# MCX_connectors_board.net
KiCad netlist of a schematic drawn in Altium Designer
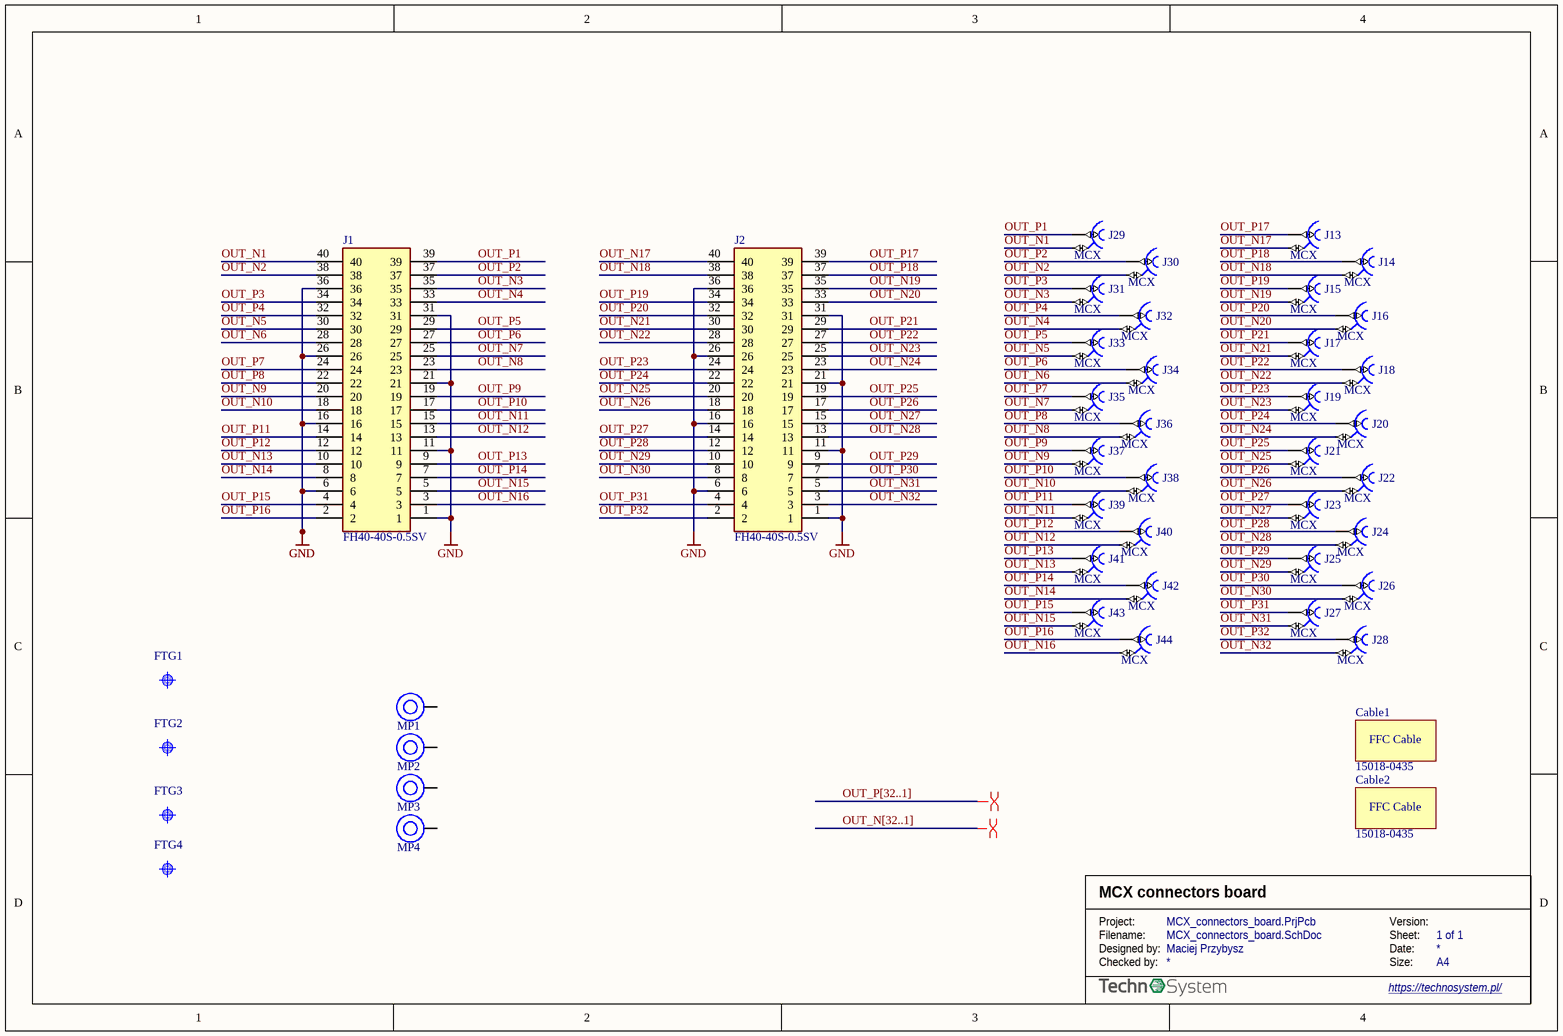
[diagram p0: MCX_connectors_board.SchDoc]

(export (version "E")
  (design (tool "Eeschema 10.0.6"))
  (components
    (comp (ref "Cable1")
      (value "15018-0435")
      (description "FFC Jumper Cables .5mm PremoFlex 40Ckt TypeA  Au 152mm")
      (libsource (lib "Integrated_Library_MP") (part "15018-0435"))
    )
    (comp (ref "Cable2")
      (value "15018-0435")
      (description "FFC Jumper Cables .5mm PremoFlex 40Ckt TypeA  Au 152mm")
      (libsource (lib "Integrated_Library_MP") (part "15018-0435"))
    )
    (comp (ref "FTG1")
      (value "Use only in PCB")
      (footprint "FIDUCIAL_TOP_C100-200")
      (description "Fiducial Target")
      (fields (field (name "PART NUMBER") "FIDUCIAL_TARGET_C100-200") (field (name "AUTHOR") "CERN DEM JLC"))
      (libsource (lib "Eletro-mechanical") (part "Fiducial Target"))
    )
    (comp (ref "FTG2")
      (value "Use only in PCB")
      (footprint "FIDUCIAL_TOP_C100-200")
      (description "Fiducial Target")
      (fields (field (name "PART NUMBER") "FIDUCIAL_TARGET_C100-200") (field (name "AUTHOR") "CERN DEM JLC"))
      (libsource (lib "Eletro-mechanical") (part "Fiducial Target"))
    )
    (comp (ref "FTG3")
      (value "Use only in PCB")
      (footprint "FIDUCIAL_TOP_C100-200")
      (description "Fiducial Target")
      (fields (field (name "PART NUMBER") "FIDUCIAL_TARGET_C100-200") (field (name "AUTHOR") "CERN DEM JLC"))
      (libsource (lib "Eletro-mechanical") (part "Fiducial Target"))
    )
    (comp (ref "FTG4")
      (value "Use only in PCB")
      (footprint "FIDUCIAL_TOP_C100-200")
      (description "Fiducial Target")
      (fields (field (name "PART NUMBER") "FIDUCIAL_TARGET_C100-200") (field (name "AUTHOR") "CERN DEM JLC"))
      (libsource (lib "Eletro-mechanical") (part "Fiducial Target"))
    )
    (comp (ref "J1")
      (value "FH40-40S-0.5SV")
      (footprint "FH4040S05SV")
      (description "Connector")
      (fields (field (name "MOUSER PART NUMBER") "798-FH40-40S-0.5SV"))
      (libsource (lib "Integrated_Library_LOADER") (part "FH40-40S-0.5SV"))
    )
    (comp (ref "J2")
      (value "FH40-40S-0.5SV")
      (footprint "FH4040S05SV")
      (description "Connector")
      (fields (field (name "MOUSER PART NUMBER") "798-FH40-40S-0.5SV"))
      (libsource (lib "Integrated_Library_LOADER") (part "FH40-40S-0.5SV"))
    )
    (comp (ref "J13")
      (value "MCX")
      (footprint "AMPHENOL_919-109J-51PX")
      (fields
        (field (name "PART NUMBER") "AMPHENOL_919-109J-51PX")
        (field (name "MANUFACTURER") "AMPHENOL")
        (field (name "MANUFACTURER PART NUMBER") "919-109J-51PX (MCX6251B1-3GT30G-50)")
        (field (name "AUTHOR") "CERN DEM BC")
      )
      (libsource (lib "Connectors") (part "Coax_1Female_1Shield"))
    )
    (comp (ref "J14")
      (value "MCX")
      (footprint "AMPHENOL_919-109J-51PX")
      (fields
        (field (name "PART NUMBER") "AMPHENOL_919-109J-51PX")
        (field (name "MANUFACTURER") "AMPHENOL")
        (field (name "MANUFACTURER PART NUMBER") "919-109J-51PX (MCX6251B1-3GT30G-50)")
        (field (name "AUTHOR") "CERN DEM BC")
      )
      (libsource (lib "Connectors") (part "Coax_1Female_1Shield"))
    )
    (comp (ref "J15")
      (value "MCX")
      (footprint "AMPHENOL_919-109J-51PX")
      (fields
        (field (name "PART NUMBER") "AMPHENOL_919-109J-51PX")
        (field (name "MANUFACTURER") "AMPHENOL")
        (field (name "MANUFACTURER PART NUMBER") "919-109J-51PX (MCX6251B1-3GT30G-50)")
        (field (name "AUTHOR") "CERN DEM BC")
      )
      (libsource (lib "Connectors") (part "Coax_1Female_1Shield"))
    )
    (comp (ref "J16")
      (value "MCX")
      (footprint "AMPHENOL_919-109J-51PX")
      (fields
        (field (name "PART NUMBER") "AMPHENOL_919-109J-51PX")
        (field (name "MANUFACTURER") "AMPHENOL")
        (field (name "MANUFACTURER PART NUMBER") "919-109J-51PX (MCX6251B1-3GT30G-50)")
        (field (name "AUTHOR") "CERN DEM BC")
      )
      (libsource (lib "Connectors") (part "Coax_1Female_1Shield"))
    )
    (comp (ref "J17")
      (value "MCX")
      (footprint "AMPHENOL_919-109J-51PX")
      (fields
        (field (name "PART NUMBER") "AMPHENOL_919-109J-51PX")
        (field (name "MANUFACTURER") "AMPHENOL")
        (field (name "MANUFACTURER PART NUMBER") "919-109J-51PX (MCX6251B1-3GT30G-50)")
        (field (name "AUTHOR") "CERN DEM BC")
      )
      (libsource (lib "Connectors") (part "Coax_1Female_1Shield"))
    )
    (comp (ref "J18")
      (value "MCX")
      (footprint "AMPHENOL_919-109J-51PX")
      (fields
        (field (name "PART NUMBER") "AMPHENOL_919-109J-51PX")
        (field (name "MANUFACTURER") "AMPHENOL")
        (field (name "MANUFACTURER PART NUMBER") "919-109J-51PX (MCX6251B1-3GT30G-50)")
        (field (name "AUTHOR") "CERN DEM BC")
      )
      (libsource (lib "Connectors") (part "Coax_1Female_1Shield"))
    )
    (comp (ref "J19")
      (value "MCX")
      (footprint "AMPHENOL_919-109J-51PX")
      (fields
        (field (name "PART NUMBER") "AMPHENOL_919-109J-51PX")
        (field (name "MANUFACTURER") "AMPHENOL")
        (field (name "MANUFACTURER PART NUMBER") "919-109J-51PX (MCX6251B1-3GT30G-50)")
        (field (name "AUTHOR") "CERN DEM BC")
      )
      (libsource (lib "Connectors") (part "Coax_1Female_1Shield"))
    )
    (comp (ref "J20")
      (value "MCX")
      (footprint "AMPHENOL_919-109J-51PX")
      (fields
        (field (name "PART NUMBER") "AMPHENOL_919-109J-51PX")
        (field (name "MANUFACTURER") "AMPHENOL")
        (field (name "MANUFACTURER PART NUMBER") "919-109J-51PX (MCX6251B1-3GT30G-50)")
        (field (name "AUTHOR") "CERN DEM BC")
      )
      (libsource (lib "Connectors") (part "Coax_1Female_1Shield"))
    )
    (comp (ref "J21")
      (value "MCX")
      (footprint "AMPHENOL_919-109J-51PX")
      (fields
        (field (name "PART NUMBER") "AMPHENOL_919-109J-51PX")
        (field (name "MANUFACTURER") "AMPHENOL")
        (field (name "MANUFACTURER PART NUMBER") "919-109J-51PX (MCX6251B1-3GT30G-50)")
        (field (name "AUTHOR") "CERN DEM BC")
      )
      (libsource (lib "Connectors") (part "Coax_1Female_1Shield"))
    )
    (comp (ref "J22")
      (value "MCX")
      (footprint "AMPHENOL_919-109J-51PX")
      (fields
        (field (name "PART NUMBER") "AMPHENOL_919-109J-51PX")
        (field (name "MANUFACTURER") "AMPHENOL")
        (field (name "MANUFACTURER PART NUMBER") "919-109J-51PX (MCX6251B1-3GT30G-50)")
        (field (name "AUTHOR") "CERN DEM BC")
      )
      (libsource (lib "Connectors") (part "Coax_1Female_1Shield"))
    )
    (comp (ref "J23")
      (value "MCX")
      (footprint "AMPHENOL_919-109J-51PX")
      (fields
        (field (name "PART NUMBER") "AMPHENOL_919-109J-51PX")
        (field (name "MANUFACTURER") "AMPHENOL")
        (field (name "MANUFACTURER PART NUMBER") "919-109J-51PX (MCX6251B1-3GT30G-50)")
        (field (name "AUTHOR") "CERN DEM BC")
      )
      (libsource (lib "Connectors") (part "Coax_1Female_1Shield"))
    )
    (comp (ref "J24")
      (value "MCX")
      (footprint "AMPHENOL_919-109J-51PX")
      (fields
        (field (name "PART NUMBER") "AMPHENOL_919-109J-51PX")
        (field (name "MANUFACTURER") "AMPHENOL")
        (field (name "MANUFACTURER PART NUMBER") "919-109J-51PX (MCX6251B1-3GT30G-50)")
        (field (name "AUTHOR") "CERN DEM BC")
      )
      (libsource (lib "Connectors") (part "Coax_1Female_1Shield"))
    )
    (comp (ref "J25")
      (value "MCX")
      (footprint "AMPHENOL_919-109J-51PX")
      (fields
        (field (name "PART NUMBER") "AMPHENOL_919-109J-51PX")
        (field (name "MANUFACTURER") "AMPHENOL")
        (field (name "MANUFACTURER PART NUMBER") "919-109J-51PX (MCX6251B1-3GT30G-50)")
        (field (name "AUTHOR") "CERN DEM BC")
      )
      (libsource (lib "Connectors") (part "Coax_1Female_1Shield"))
    )
    (comp (ref "J26")
      (value "MCX")
      (footprint "AMPHENOL_919-109J-51PX")
      (fields
        (field (name "PART NUMBER") "AMPHENOL_919-109J-51PX")
        (field (name "MANUFACTURER") "AMPHENOL")
        (field (name "MANUFACTURER PART NUMBER") "919-109J-51PX (MCX6251B1-3GT30G-50)")
        (field (name "AUTHOR") "CERN DEM BC")
      )
      (libsource (lib "Connectors") (part "Coax_1Female_1Shield"))
    )
    (comp (ref "J27")
      (value "MCX")
      (footprint "AMPHENOL_919-109J-51PX")
      (fields
        (field (name "PART NUMBER") "AMPHENOL_919-109J-51PX")
        (field (name "MANUFACTURER") "AMPHENOL")
        (field (name "MANUFACTURER PART NUMBER") "919-109J-51PX (MCX6251B1-3GT30G-50)")
        (field (name "AUTHOR") "CERN DEM BC")
      )
      (libsource (lib "Connectors") (part "Coax_1Female_1Shield"))
    )
    (comp (ref "J28")
      (value "MCX")
      (footprint "AMPHENOL_919-109J-51PX")
      (fields
        (field (name "PART NUMBER") "AMPHENOL_919-109J-51PX")
        (field (name "MANUFACTURER") "AMPHENOL")
        (field (name "MANUFACTURER PART NUMBER") "919-109J-51PX (MCX6251B1-3GT30G-50)")
        (field (name "AUTHOR") "CERN DEM BC")
      )
      (libsource (lib "Connectors") (part "Coax_1Female_1Shield"))
    )
    (comp (ref "J29")
      (value "MCX")
      (footprint "AMPHENOL_919-109J-51PX")
      (fields
        (field (name "PART NUMBER") "AMPHENOL_919-109J-51PX")
        (field (name "MANUFACTURER") "AMPHENOL")
        (field (name "MANUFACTURER PART NUMBER") "919-109J-51PX (MCX6251B1-3GT30G-50)")
        (field (name "AUTHOR") "CERN DEM BC")
      )
      (libsource (lib "Connectors") (part "Coax_1Female_1Shield"))
    )
    (comp (ref "J30")
      (value "MCX")
      (footprint "AMPHENOL_919-109J-51PX")
      (fields
        (field (name "PART NUMBER") "AMPHENOL_919-109J-51PX")
        (field (name "MANUFACTURER") "AMPHENOL")
        (field (name "MANUFACTURER PART NUMBER") "919-109J-51PX (MCX6251B1-3GT30G-50)")
        (field (name "AUTHOR") "CERN DEM BC")
      )
      (libsource (lib "Connectors") (part "Coax_1Female_1Shield"))
    )
    (comp (ref "J31")
      (value "MCX")
      (footprint "AMPHENOL_919-109J-51PX")
      (fields
        (field (name "PART NUMBER") "AMPHENOL_919-109J-51PX")
        (field (name "MANUFACTURER") "AMPHENOL")
        (field (name "MANUFACTURER PART NUMBER") "919-109J-51PX (MCX6251B1-3GT30G-50)")
        (field (name "AUTHOR") "CERN DEM BC")
      )
      (libsource (lib "Connectors") (part "Coax_1Female_1Shield"))
    )
    (comp (ref "J32")
      (value "MCX")
      (footprint "AMPHENOL_919-109J-51PX")
      (fields
        (field (name "PART NUMBER") "AMPHENOL_919-109J-51PX")
        (field (name "MANUFACTURER") "AMPHENOL")
        (field (name "MANUFACTURER PART NUMBER") "919-109J-51PX (MCX6251B1-3GT30G-50)")
        (field (name "AUTHOR") "CERN DEM BC")
      )
      (libsource (lib "Connectors") (part "Coax_1Female_1Shield"))
    )
    (comp (ref "J33")
      (value "MCX")
      (footprint "AMPHENOL_919-109J-51PX")
      (fields
        (field (name "PART NUMBER") "AMPHENOL_919-109J-51PX")
        (field (name "MANUFACTURER") "AMPHENOL")
        (field (name "MANUFACTURER PART NUMBER") "919-109J-51PX (MCX6251B1-3GT30G-50)")
        (field (name "AUTHOR") "CERN DEM BC")
      )
      (libsource (lib "Connectors") (part "Coax_1Female_1Shield"))
    )
    (comp (ref "J34")
      (value "MCX")
      (footprint "AMPHENOL_919-109J-51PX")
      (fields
        (field (name "PART NUMBER") "AMPHENOL_919-109J-51PX")
        (field (name "MANUFACTURER") "AMPHENOL")
        (field (name "MANUFACTURER PART NUMBER") "919-109J-51PX (MCX6251B1-3GT30G-50)")
        (field (name "AUTHOR") "CERN DEM BC")
      )
      (libsource (lib "Connectors") (part "Coax_1Female_1Shield"))
    )
    (comp (ref "J35")
      (value "MCX")
      (footprint "AMPHENOL_919-109J-51PX")
      (fields
        (field (name "PART NUMBER") "AMPHENOL_919-109J-51PX")
        (field (name "MANUFACTURER") "AMPHENOL")
        (field (name "MANUFACTURER PART NUMBER") "919-109J-51PX (MCX6251B1-3GT30G-50)")
        (field (name "AUTHOR") "CERN DEM BC")
      )
      (libsource (lib "Connectors") (part "Coax_1Female_1Shield"))
    )
    (comp (ref "J36")
      (value "MCX")
      (footprint "AMPHENOL_919-109J-51PX")
      (fields
        (field (name "PART NUMBER") "AMPHENOL_919-109J-51PX")
        (field (name "MANUFACTURER") "AMPHENOL")
        (field (name "MANUFACTURER PART NUMBER") "919-109J-51PX (MCX6251B1-3GT30G-50)")
        (field (name "AUTHOR") "CERN DEM BC")
      )
      (libsource (lib "Connectors") (part "Coax_1Female_1Shield"))
    )
    (comp (ref "J37")
      (value "MCX")
      (footprint "AMPHENOL_919-109J-51PX")
      (fields
        (field (name "PART NUMBER") "AMPHENOL_919-109J-51PX")
        (field (name "MANUFACTURER") "AMPHENOL")
        (field (name "MANUFACTURER PART NUMBER") "919-109J-51PX (MCX6251B1-3GT30G-50)")
        (field (name "AUTHOR") "CERN DEM BC")
      )
      (libsource (lib "Connectors") (part "Coax_1Female_1Shield"))
    )
    (comp (ref "J38")
      (value "MCX")
      (footprint "AMPHENOL_919-109J-51PX")
      (fields
        (field (name "PART NUMBER") "AMPHENOL_919-109J-51PX")
        (field (name "MANUFACTURER") "AMPHENOL")
        (field (name "MANUFACTURER PART NUMBER") "919-109J-51PX (MCX6251B1-3GT30G-50)")
        (field (name "AUTHOR") "CERN DEM BC")
      )
      (libsource (lib "Connectors") (part "Coax_1Female_1Shield"))
    )
    (comp (ref "J39")
      (value "MCX")
      (footprint "AMPHENOL_919-109J-51PX")
      (fields
        (field (name "PART NUMBER") "AMPHENOL_919-109J-51PX")
        (field (name "MANUFACTURER") "AMPHENOL")
        (field (name "MANUFACTURER PART NUMBER") "919-109J-51PX (MCX6251B1-3GT30G-50)")
        (field (name "AUTHOR") "CERN DEM BC")
      )
      (libsource (lib "Connectors") (part "Coax_1Female_1Shield"))
    )
    (comp (ref "J40")
      (value "MCX")
      (footprint "AMPHENOL_919-109J-51PX")
      (fields
        (field (name "PART NUMBER") "AMPHENOL_919-109J-51PX")
        (field (name "MANUFACTURER") "AMPHENOL")
        (field (name "MANUFACTURER PART NUMBER") "919-109J-51PX (MCX6251B1-3GT30G-50)")
        (field (name "AUTHOR") "CERN DEM BC")
      )
      (libsource (lib "Connectors") (part "Coax_1Female_1Shield"))
    )
    (comp (ref "J41")
      (value "MCX")
      (footprint "AMPHENOL_919-109J-51PX")
      (fields
        (field (name "PART NUMBER") "AMPHENOL_919-109J-51PX")
        (field (name "MANUFACTURER") "AMPHENOL")
        (field (name "MANUFACTURER PART NUMBER") "919-109J-51PX (MCX6251B1-3GT30G-50)")
        (field (name "AUTHOR") "CERN DEM BC")
      )
      (libsource (lib "Connectors") (part "Coax_1Female_1Shield"))
    )
    (comp (ref "J42")
      (value "MCX")
      (footprint "AMPHENOL_919-109J-51PX")
      (fields
        (field (name "PART NUMBER") "AMPHENOL_919-109J-51PX")
        (field (name "MANUFACTURER") "AMPHENOL")
        (field (name "MANUFACTURER PART NUMBER") "919-109J-51PX (MCX6251B1-3GT30G-50)")
        (field (name "AUTHOR") "CERN DEM BC")
      )
      (libsource (lib "Connectors") (part "Coax_1Female_1Shield"))
    )
    (comp (ref "J43")
      (value "MCX")
      (footprint "AMPHENOL_919-109J-51PX")
      (fields
        (field (name "PART NUMBER") "AMPHENOL_919-109J-51PX")
        (field (name "MANUFACTURER") "AMPHENOL")
        (field (name "MANUFACTURER PART NUMBER") "919-109J-51PX (MCX6251B1-3GT30G-50)")
        (field (name "AUTHOR") "CERN DEM BC")
      )
      (libsource (lib "Connectors") (part "Coax_1Female_1Shield"))
    )
    (comp (ref "J44")
      (value "MCX")
      (footprint "AMPHENOL_919-109J-51PX")
      (fields
        (field (name "PART NUMBER") "AMPHENOL_919-109J-51PX")
        (field (name "MANUFACTURER") "AMPHENOL")
        (field (name "MANUFACTURER PART NUMBER") "919-109J-51PX (MCX6251B1-3GT30G-50)")
        (field (name "AUTHOR") "CERN DEM BC")
      )
      (libsource (lib "Connectors") (part "Coax_1Female_1Shield"))
    )
    (comp (ref "MP1")
      (value "9774035151R")
      (footprint "9774035151")
      (description "WA-SMSI SMT Steel Spacer with internal Thread, OD 5.1mm, M2.5 x 3.5mm")
      (fields (field (name "MANUFACTURER") "Wurth Elektronik"))
      (libsource (lib "Altium_WA-SMSI (rev22a)") (part "9774035151R"))
    )
    (comp (ref "MP2")
      (value "9774035151R")
      (footprint "9774035151")
      (description "WA-SMSI SMT Steel Spacer with internal Thread, OD 5.1mm, M2.5 x 3.5mm")
      (fields (field (name "MANUFACTURER") "Wurth Elektronik"))
      (libsource (lib "Altium_WA-SMSI (rev22a)") (part "9774035151R"))
    )
    (comp (ref "MP3")
      (value "9774035151R")
      (footprint "9774035151")
      (description "WA-SMSI SMT Steel Spacer with internal Thread, OD 5.1mm, M2.5 x 3.5mm")
      (fields (field (name "MANUFACTURER") "Wurth Elektronik"))
      (libsource (lib "Altium_WA-SMSI (rev22a)") (part "9774035151R"))
    )
    (comp (ref "MP4")
      (value "9774035151R")
      (footprint "9774035151")
      (description "WA-SMSI SMT Steel Spacer with internal Thread, OD 5.1mm, M2.5 x 3.5mm")
      (fields (field (name "MANUFACTURER") "Wurth Elektronik"))
      (libsource (lib "Altium_WA-SMSI (rev22a)") (part "9774035151R"))
    )
  )
  (nets
    (net (code "1") (name "/OUT_N1") (class "Default")
      (node (ref "J1") (pin "40") (pinfunction "40_40") (pintype "passive"))
      (node (ref "J29") (pin "2") (pinfunction "2_2") (pintype "bidirectional"))
    )
    (net (code "2") (name "/OUT_N2") (class "Default")
      (node (ref "J1") (pin "38") (pinfunction "38_38") (pintype "passive"))
      (node (ref "J30") (pin "2") (pinfunction "2_2") (pintype "bidirectional"))
    )
    (net (code "3") (name "/OUT_N3") (class "Default")
      (node (ref "J1") (pin "35") (pinfunction "35_35") (pintype "passive"))
      (node (ref "J31") (pin "2") (pinfunction "2_2") (pintype "bidirectional"))
    )
    (net (code "4") (name "/OUT_N4") (class "Default")
      (node (ref "J1") (pin "33") (pinfunction "33_33") (pintype "passive"))
      (node (ref "J32") (pin "2") (pinfunction "2_2") (pintype "bidirectional"))
    )
    (net (code "5") (name "/OUT_N5") (class "Default")
      (node (ref "J1") (pin "30") (pinfunction "30_30") (pintype "passive"))
      (node (ref "J33") (pin "2") (pinfunction "2_2") (pintype "bidirectional"))
    )
    (net (code "6") (name "/OUT_N6") (class "Default")
      (node (ref "J1") (pin "28") (pinfunction "28_28") (pintype "passive"))
      (node (ref "J34") (pin "2") (pinfunction "2_2") (pintype "bidirectional"))
    )
    (net (code "7") (name "/OUT_N7") (class "Default")
      (node (ref "J1") (pin "25") (pinfunction "25_25") (pintype "passive"))
      (node (ref "J35") (pin "2") (pinfunction "2_2") (pintype "bidirectional"))
    )
    (net (code "8") (name "/OUT_N8") (class "Default")
      (node (ref "J1") (pin "23") (pinfunction "23_23") (pintype "passive"))
      (node (ref "J36") (pin "2") (pinfunction "2_2") (pintype "bidirectional"))
    )
    (net (code "9") (name "/OUT_N9") (class "Default")
      (node (ref "J1") (pin "20") (pinfunction "20_20") (pintype "passive"))
      (node (ref "J37") (pin "2") (pinfunction "2_2") (pintype "bidirectional"))
    )
    (net (code "10") (name "/OUT_N10") (class "Default")
      (node (ref "J1") (pin "18") (pinfunction "18_18") (pintype "passive"))
      (node (ref "J38") (pin "2") (pinfunction "2_2") (pintype "bidirectional"))
    )
    (net (code "11") (name "/OUT_N11") (class "Default")
      (node (ref "J1") (pin "15") (pinfunction "15_15") (pintype "passive"))
      (node (ref "J39") (pin "2") (pinfunction "2_2") (pintype "bidirectional"))
    )
    (net (code "12") (name "/OUT_N12") (class "Default")
      (node (ref "J1") (pin "13") (pinfunction "13_13") (pintype "passive"))
      (node (ref "J40") (pin "2") (pinfunction "2_2") (pintype "bidirectional"))
    )
    (net (code "13") (name "/OUT_N13") (class "Default")
      (node (ref "J1") (pin "10") (pinfunction "10_10") (pintype "passive"))
      (node (ref "J41") (pin "2") (pinfunction "2_2") (pintype "bidirectional"))
    )
    (net (code "14") (name "/OUT_N14") (class "Default")
      (node (ref "J1") (pin "8") (pinfunction "8_8") (pintype "passive"))
      (node (ref "J42") (pin "2") (pinfunction "2_2") (pintype "bidirectional"))
    )
    (net (code "15") (name "/OUT_N15") (class "Default")
      (node (ref "J1") (pin "5") (pinfunction "5_5") (pintype "passive"))
      (node (ref "J43") (pin "2") (pinfunction "2_2") (pintype "bidirectional"))
    )
    (net (code "16") (name "/OUT_N16") (class "Default")
      (node (ref "J1") (pin "3") (pinfunction "3_3") (pintype "passive"))
      (node (ref "J44") (pin "2") (pinfunction "2_2") (pintype "bidirectional"))
    )
    (net (code "17") (name "/OUT_N17") (class "Default")
      (node (ref "J13") (pin "2") (pinfunction "2_2") (pintype "bidirectional"))
      (node (ref "J2") (pin "40") (pinfunction "40_40") (pintype "passive"))
    )
    (net (code "18") (name "/OUT_N18") (class "Default")
      (node (ref "J14") (pin "2") (pinfunction "2_2") (pintype "bidirectional"))
      (node (ref "J2") (pin "38") (pinfunction "38_38") (pintype "passive"))
    )
    (net (code "19") (name "/OUT_N19") (class "Default")
      (node (ref "J15") (pin "2") (pinfunction "2_2") (pintype "bidirectional"))
      (node (ref "J2") (pin "35") (pinfunction "35_35") (pintype "passive"))
    )
    (net (code "20") (name "/OUT_N20") (class "Default")
      (node (ref "J16") (pin "2") (pinfunction "2_2") (pintype "bidirectional"))
      (node (ref "J2") (pin "33") (pinfunction "33_33") (pintype "passive"))
    )
    (net (code "21") (name "/OUT_N21") (class "Default")
      (node (ref "J17") (pin "2") (pinfunction "2_2") (pintype "bidirectional"))
      (node (ref "J2") (pin "30") (pinfunction "30_30") (pintype "passive"))
    )
    (net (code "22") (name "/OUT_N22") (class "Default")
      (node (ref "J18") (pin "2") (pinfunction "2_2") (pintype "bidirectional"))
      (node (ref "J2") (pin "28") (pinfunction "28_28") (pintype "passive"))
    )
    (net (code "23") (name "/OUT_N23") (class "Default")
      (node (ref "J19") (pin "2") (pinfunction "2_2") (pintype "bidirectional"))
      (node (ref "J2") (pin "25") (pinfunction "25_25") (pintype "passive"))
    )
    (net (code "24") (name "/OUT_N24") (class "Default")
      (node (ref "J2") (pin "23") (pinfunction "23_23") (pintype "passive"))
      (node (ref "J20") (pin "2") (pinfunction "2_2") (pintype "bidirectional"))
    )
    (net (code "25") (name "/OUT_N25") (class "Default")
      (node (ref "J2") (pin "20") (pinfunction "20_20") (pintype "passive"))
      (node (ref "J21") (pin "2") (pinfunction "2_2") (pintype "bidirectional"))
    )
    (net (code "26") (name "/OUT_N26") (class "Default")
      (node (ref "J2") (pin "18") (pinfunction "18_18") (pintype "passive"))
      (node (ref "J22") (pin "2") (pinfunction "2_2") (pintype "bidirectional"))
    )
    (net (code "27") (name "/OUT_N27") (class "Default")
      (node (ref "J2") (pin "15") (pinfunction "15_15") (pintype "passive"))
      (node (ref "J23") (pin "2") (pinfunction "2_2") (pintype "bidirectional"))
    )
    (net (code "28") (name "/OUT_N28") (class "Default")
      (node (ref "J2") (pin "13") (pinfunction "13_13") (pintype "passive"))
      (node (ref "J24") (pin "2") (pinfunction "2_2") (pintype "bidirectional"))
    )
    (net (code "29") (name "/OUT_N29") (class "Default")
      (node (ref "J2") (pin "10") (pinfunction "10_10") (pintype "passive"))
      (node (ref "J25") (pin "2") (pinfunction "2_2") (pintype "bidirectional"))
    )
    (net (code "30") (name "/OUT_N30") (class "Default")
      (node (ref "J2") (pin "8") (pinfunction "8_8") (pintype "passive"))
      (node (ref "J26") (pin "2") (pinfunction "2_2") (pintype "bidirectional"))
    )
    (net (code "31") (name "/OUT_N31") (class "Default")
      (node (ref "J2") (pin "5") (pinfunction "5_5") (pintype "passive"))
      (node (ref "J27") (pin "2") (pinfunction "2_2") (pintype "bidirectional"))
    )
    (net (code "32") (name "/OUT_N32") (class "Default")
      (node (ref "J2") (pin "3") (pinfunction "3_3") (pintype "passive"))
      (node (ref "J28") (pin "2") (pinfunction "2_2") (pintype "bidirectional"))
    )
    (net (code "34") (name "/OUT_P1") (class "Default")
      (node (ref "J1") (pin "39") (pinfunction "39_39") (pintype "passive"))
      (node (ref "J29") (pin "1") (pinfunction "1_1") (pintype "bidirectional"))
    )
    (net (code "35") (name "/OUT_P2") (class "Default")
      (node (ref "J1") (pin "37") (pinfunction "37_37") (pintype "passive"))
      (node (ref "J30") (pin "1") (pinfunction "1_1") (pintype "bidirectional"))
    )
    (net (code "36") (name "/OUT_P3") (class "Default")
      (node (ref "J1") (pin "34") (pinfunction "34_34") (pintype "passive"))
      (node (ref "J31") (pin "1") (pinfunction "1_1") (pintype "bidirectional"))
    )
    (net (code "37") (name "/OUT_P4") (class "Default")
      (node (ref "J1") (pin "32") (pinfunction "32_32") (pintype "passive"))
      (node (ref "J32") (pin "1") (pinfunction "1_1") (pintype "bidirectional"))
    )
    (net (code "38") (name "/OUT_P5") (class "Default")
      (node (ref "J1") (pin "29") (pinfunction "29_29") (pintype "passive"))
      (node (ref "J33") (pin "1") (pinfunction "1_1") (pintype "bidirectional"))
    )
    (net (code "39") (name "/OUT_P6") (class "Default")
      (node (ref "J1") (pin "27") (pinfunction "27_27") (pintype "passive"))
      (node (ref "J34") (pin "1") (pinfunction "1_1") (pintype "bidirectional"))
    )
    (net (code "40") (name "/OUT_P7") (class "Default")
      (node (ref "J1") (pin "24") (pinfunction "24_24") (pintype "passive"))
      (node (ref "J35") (pin "1") (pinfunction "1_1") (pintype "bidirectional"))
    )
    (net (code "41") (name "/OUT_P8") (class "Default")
      (node (ref "J1") (pin "22") (pinfunction "22_22") (pintype "passive"))
      (node (ref "J36") (pin "1") (pinfunction "1_1") (pintype "bidirectional"))
    )
    (net (code "42") (name "/OUT_P9") (class "Default")
      (node (ref "J1") (pin "19") (pinfunction "19_19") (pintype "passive"))
      (node (ref "J37") (pin "1") (pinfunction "1_1") (pintype "bidirectional"))
    )
    (net (code "43") (name "/OUT_P10") (class "Default")
      (node (ref "J1") (pin "17") (pinfunction "17_17") (pintype "passive"))
      (node (ref "J38") (pin "1") (pinfunction "1_1") (pintype "bidirectional"))
    )
    (net (code "44") (name "/OUT_P11") (class "Default")
      (node (ref "J1") (pin "14") (pinfunction "14_14") (pintype "passive"))
      (node (ref "J39") (pin "1") (pinfunction "1_1") (pintype "bidirectional"))
    )
    (net (code "45") (name "/OUT_P12") (class "Default")
      (node (ref "J1") (pin "12") (pinfunction "12_12") (pintype "passive"))
      (node (ref "J40") (pin "1") (pinfunction "1_1") (pintype "bidirectional"))
    )
    (net (code "46") (name "/OUT_P13") (class "Default")
      (node (ref "J1") (pin "9") (pinfunction "9_9") (pintype "passive"))
      (node (ref "J41") (pin "1") (pinfunction "1_1") (pintype "bidirectional"))
    )
    (net (code "47") (name "/OUT_P14") (class "Default")
      (node (ref "J1") (pin "7") (pinfunction "7_7") (pintype "passive"))
      (node (ref "J42") (pin "1") (pinfunction "1_1") (pintype "bidirectional"))
    )
    (net (code "48") (name "/OUT_P15") (class "Default")
      (node (ref "J1") (pin "4") (pinfunction "4_4") (pintype "passive"))
      (node (ref "J43") (pin "1") (pinfunction "1_1") (pintype "bidirectional"))
    )
    (net (code "49") (name "/OUT_P16") (class "Default")
      (node (ref "J1") (pin "2") (pinfunction "2_2") (pintype "passive"))
      (node (ref "J44") (pin "1") (pinfunction "1_1") (pintype "bidirectional"))
    )
    (net (code "50") (name "/OUT_P17") (class "Default")
      (node (ref "J13") (pin "1") (pinfunction "1_1") (pintype "bidirectional"))
      (node (ref "J2") (pin "39") (pinfunction "39_39") (pintype "passive"))
    )
    (net (code "51") (name "/OUT_P18") (class "Default")
      (node (ref "J14") (pin "1") (pinfunction "1_1") (pintype "bidirectional"))
      (node (ref "J2") (pin "37") (pinfunction "37_37") (pintype "passive"))
    )
    (net (code "52") (name "/OUT_P19") (class "Default")
      (node (ref "J15") (pin "1") (pinfunction "1_1") (pintype "bidirectional"))
      (node (ref "J2") (pin "34") (pinfunction "34_34") (pintype "passive"))
    )
    (net (code "53") (name "/OUT_P20") (class "Default")
      (node (ref "J16") (pin "1") (pinfunction "1_1") (pintype "bidirectional"))
      (node (ref "J2") (pin "32") (pinfunction "32_32") (pintype "passive"))
    )
    (net (code "54") (name "/OUT_P21") (class "Default")
      (node (ref "J17") (pin "1") (pinfunction "1_1") (pintype "bidirectional"))
      (node (ref "J2") (pin "29") (pinfunction "29_29") (pintype "passive"))
    )
    (net (code "55") (name "/OUT_P22") (class "Default")
      (node (ref "J18") (pin "1") (pinfunction "1_1") (pintype "bidirectional"))
      (node (ref "J2") (pin "27") (pinfunction "27_27") (pintype "passive"))
    )
    (net (code "56") (name "/OUT_P23") (class "Default")
      (node (ref "J19") (pin "1") (pinfunction "1_1") (pintype "bidirectional"))
      (node (ref "J2") (pin "24") (pinfunction "24_24") (pintype "passive"))
    )
    (net (code "57") (name "/OUT_P24") (class "Default")
      (node (ref "J2") (pin "22") (pinfunction "22_22") (pintype "passive"))
      (node (ref "J20") (pin "1") (pinfunction "1_1") (pintype "bidirectional"))
    )
    (net (code "58") (name "/OUT_P25") (class "Default")
      (node (ref "J2") (pin "19") (pinfunction "19_19") (pintype "passive"))
      (node (ref "J21") (pin "1") (pinfunction "1_1") (pintype "bidirectional"))
    )
    (net (code "59") (name "/OUT_P26") (class "Default")
      (node (ref "J2") (pin "17") (pinfunction "17_17") (pintype "passive"))
      (node (ref "J22") (pin "1") (pinfunction "1_1") (pintype "bidirectional"))
    )
    (net (code "60") (name "/OUT_P27") (class "Default")
      (node (ref "J2") (pin "14") (pinfunction "14_14") (pintype "passive"))
      (node (ref "J23") (pin "1") (pinfunction "1_1") (pintype "bidirectional"))
    )
    (net (code "61") (name "/OUT_P28") (class "Default")
      (node (ref "J2") (pin "12") (pinfunction "12_12") (pintype "passive"))
      (node (ref "J24") (pin "1") (pinfunction "1_1") (pintype "bidirectional"))
    )
    (net (code "62") (name "/OUT_P29") (class "Default")
      (node (ref "J2") (pin "9") (pinfunction "9_9") (pintype "passive"))
      (node (ref "J25") (pin "1") (pinfunction "1_1") (pintype "bidirectional"))
    )
    (net (code "63") (name "/OUT_P30") (class "Default")
      (node (ref "J2") (pin "7") (pinfunction "7_7") (pintype "passive"))
      (node (ref "J26") (pin "1") (pinfunction "1_1") (pintype "bidirectional"))
    )
    (net (code "64") (name "/OUT_P31") (class "Default")
      (node (ref "J2") (pin "4") (pinfunction "4_4") (pintype "passive"))
      (node (ref "J27") (pin "1") (pinfunction "1_1") (pintype "bidirectional"))
    )
    (net (code "65") (name "/OUT_P32") (class "Default")
      (node (ref "J2") (pin "2") (pinfunction "2_2") (pintype "passive"))
      (node (ref "J28") (pin "1") (pinfunction "1_1") (pintype "bidirectional"))
    )
    (net (code "67") (name "GND") (class "Default")
      (node (ref "J1") (pin "1") (pinfunction "1_1") (pintype "passive"))
      (node (ref "J1") (pin "11") (pinfunction "11_11") (pintype "passive"))
      (node (ref "J1") (pin "16") (pinfunction "16_16") (pintype "passive"))
      (node (ref "J1") (pin "21") (pinfunction "21_21") (pintype "passive"))
      (node (ref "J1") (pin "26") (pinfunction "26_26") (pintype "passive"))
      (node (ref "J1") (pin "31") (pinfunction "31_31") (pintype "passive"))
      (node (ref "J1") (pin "36") (pinfunction "36_36") (pintype "passive"))
      (node (ref "J1") (pin "6") (pinfunction "6_6") (pintype "passive"))
      (node (ref "J2") (pin "1") (pinfunction "1_1") (pintype "passive"))
      (node (ref "J2") (pin "11") (pinfunction "11_11") (pintype "passive"))
      (node (ref "J2") (pin "16") (pinfunction "16_16") (pintype "passive"))
      (node (ref "J2") (pin "21") (pinfunction "21_21") (pintype "passive"))
      (node (ref "J2") (pin "26") (pinfunction "26_26") (pintype "passive"))
      (node (ref "J2") (pin "31") (pinfunction "31_31") (pintype "passive"))
      (node (ref "J2") (pin "36") (pinfunction "36_36") (pintype "passive"))
      (node (ref "J2") (pin "6") (pinfunction "6_6") (pintype "passive"))
    )
    (net (code "68") (name "unconnected-(MP1-Pad1)") (class "Default")
      (node (ref "MP1") (pin "1") (pinfunction "1_1") (pintype "passive"))
    )
    (net (code "69") (name "unconnected-(MP2-Pad1)") (class "Default")
      (node (ref "MP2") (pin "1") (pinfunction "1_1") (pintype "passive"))
    )
    (net (code "70") (name "unconnected-(MP3-Pad1)") (class "Default")
      (node (ref "MP3") (pin "1") (pinfunction "1_1") (pintype "passive"))
    )
    (net (code "71") (name "unconnected-(MP4-Pad1)") (class "Default")
      (node (ref "MP4") (pin "1") (pinfunction "1_1") (pintype "passive"))
    )
  )
)
